# Digital_Isolation.net
KiCad netlist of a schematic drawn in Altium Designer
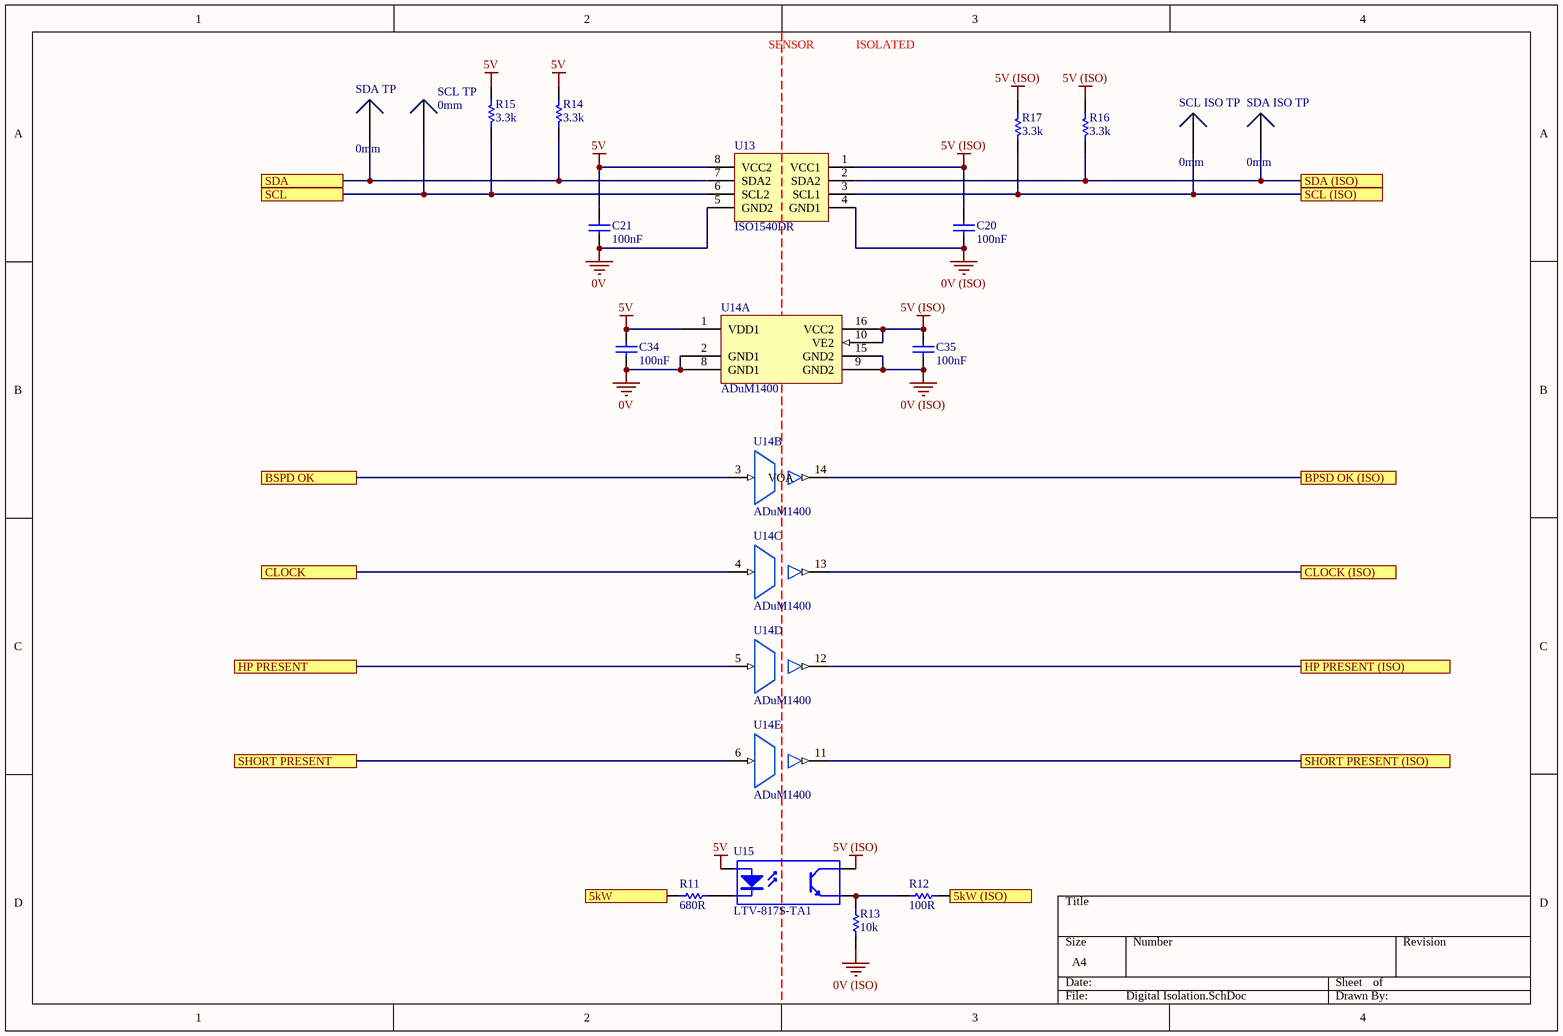
[diagram p0: Digital Isolation.SchDoc]

(export (version "E")
  (design (tool "Eeschema 10.0.6"))
  (components
    (comp (ref "C20")
      (value "100nF")
      (footprint "0805")
      (fields
        (field (name "PART NUMBER") "GCM21BR71E104KA37L")
        (field (name "TOLERANCE") "10%")
        (field (name "MANUFACTURER") "muRata")
      )
      (libsource (lib "ts_20-standard-library") (part "Capacitor"))
    )
    (comp (ref "C21")
      (value "100nF")
      (footprint "0805")
      (fields
        (field (name "PART NUMBER") "GCM21BR71E104KA37L")
        (field (name "TOLERANCE") "10%")
        (field (name "MANUFACTURER") "muRata")
      )
      (libsource (lib "ts_20-standard-library") (part "Capacitor"))
    )
    (comp (ref "C34")
      (value "100nF")
      (footprint "0805")
      (fields
        (field (name "PART NUMBER") "GCM21BR71E104KA37L")
        (field (name "TOLERANCE") "10%")
        (field (name "MANUFACTURER") "muRata")
      )
      (libsource (lib "ts_20-standard-library") (part "Capacitor"))
    )
    (comp (ref "C35")
      (value "100nF")
      (footprint "0805")
      (fields
        (field (name "PART NUMBER") "GCM21BR71E104KA37L")
        (field (name "TOLERANCE") "10%")
        (field (name "MANUFACTURER") "muRata")
      )
      (libsource (lib "ts_20-standard-library") (part "Capacitor"))
    )
    (comp (ref "R11")
      (value "680R")
      (footprint "0805")
      (fields
        (field (name "PART NUMBER") "RC0805FR07680RL")
        (field (name "MANUFACTURER") "YAGEO")
        (field (name "TOLERANCE") "0.01")
      )
      (libsource (lib "ts_20-standard-library") (part "Resistor"))
    )
    (comp (ref "R12")
      (value "100R")
      (footprint "0805")
      (fields
        (field (name "PART NUMBER") "RC0805FR07100RL")
        (field (name "MANUFACTURER") "YAGEO")
        (field (name "TOLERANCE") "0.01")
      )
      (libsource (lib "ts_20-standard-library") (part "Resistor"))
    )
    (comp (ref "R13")
      (value "10k")
      (footprint "0805")
      (fields
        (field (name "PART NUMBER") "RC0805FR0710KL")
        (field (name "MANUFACTURER") "YAGEO")
        (field (name "TOLERANCE") "0.01")
      )
      (libsource (lib "ts_20-standard-library") (part "Resistor"))
    )
    (comp (ref "R14")
      (value "3.3k")
      (footprint "0805")
      (fields
        (field (name "PART NUMBER") "RC0805FR073K3L")
        (field (name "MANUFACTURER") "YAGEO")
        (field (name "TOLERANCE") "0.01")
      )
      (libsource (lib "ts_20-standard-library") (part "Resistor"))
    )
    (comp (ref "R15")
      (value "3.3k")
      (footprint "0805")
      (fields
        (field (name "PART NUMBER") "RC0805FR073K3L")
        (field (name "MANUFACTURER") "YAGEO")
        (field (name "TOLERANCE") "0.01")
      )
      (libsource (lib "ts_20-standard-library") (part "Resistor"))
    )
    (comp (ref "R16")
      (value "3.3k")
      (footprint "0805")
      (fields
        (field (name "PART NUMBER") "RC0805FR073K3L")
        (field (name "MANUFACTURER") "YAGEO")
        (field (name "TOLERANCE") "0.01")
      )
      (libsource (lib "ts_20-standard-library") (part "Resistor"))
    )
    (comp (ref "R17")
      (value "3.3k")
      (footprint "0805")
      (fields
        (field (name "PART NUMBER") "RC0805FR073K3L")
        (field (name "MANUFACTURER") "YAGEO")
        (field (name "TOLERANCE") "0.01")
      )
      (libsource (lib "ts_20-standard-library") (part "Resistor"))
    )
    (comp (ref "SCL ISO TP")
      (value "0mm")
      (footprint "SMD Test Point")
      (fields (field (name "PART NUMBER") "SMD Test Point") (field (name "CONTACT") "NA"))
      (libsource (lib "ts_20-standard-connectors") (part "Test Point"))
    )
    (comp (ref "SCL TP")
      (value "0mm")
      (footprint "SMD Test Point")
      (fields (field (name "PART NUMBER") "SMD Test Point") (field (name "CONTACT") "NA"))
      (libsource (lib "ts_20-standard-connectors") (part "Test Point"))
    )
    (comp (ref "SDA ISO TP")
      (value "0mm")
      (footprint "SMD Test Point")
      (fields (field (name "PART NUMBER") "SMD Test Point") (field (name "CONTACT") "NA"))
      (libsource (lib "ts_20-standard-connectors") (part "Test Point"))
    )
    (comp (ref "SDA TP")
      (value "0mm")
      (footprint "SMD Test Point")
      (fields (field (name "PART NUMBER") "SMD Test Point") (field (name "CONTACT") "NA"))
      (libsource (lib "ts_20-standard-connectors") (part "Test Point"))
    )
    (comp (ref "U13")
      (value "ISO1540DR")
      (footprint "TI 8-SOIC")
      (description "I2C Digital Isolator (Multichannel)")
      (fields
        (field (name "MANUFACTURER") "Texas Instruments")
        (field (name "DIGIKEY PART NUMBER") "296-34871-1-ND")
      )
      (libsource (lib "ts_20-standard-library") (part "ISO1540DR"))
    )
    (comp (ref "U14")
      (value "ADuM1400")
      (footprint "AD 16-SOIC")
      (fields
        (field (name "MANUFACTURER") "Analog Devices")
        (field (name "DIGIKEY PART NUMBER") "ADUM1400WSRWZ-ND")
      )
      (libsource (lib "ts_20-standard-library") (part "ADuM1400"))
    )
    (comp (ref "U15")
      (value "LTV-817S-TA1")
      (footprint "ON 4-SMD")
      (description "35V 50ma Optocoupler (VF=1.2V)")
      (fields
        (field (name "MANUFACTURER") "Lite-On Inc")
        (field (name "DIGIKEY PART NUMBER") "160-1893-2-ND")
      )
      (libsource (lib "ts_20-standard-library") (part "LTV-817S-TA1"))
    )
  )
  (nets
    (net (code "1") (name "/5kW") (class "Default")
      (node (ref "R11") (pin "2") (pinfunction "2_2") (pintype "passive"))
    )
    (net (code "2") (name "/5kW (ISO)") (class "Default")
      (node (ref "R12") (pin "2") (pinfunction "2_2") (pintype "passive"))
    )
    (net (code "3") (name "/BPSD OK (ISO)") (class "Default")
      (node (ref "U14") (pin "14") (pinfunction "VOA_14") (pintype "output"))
    )
    (net (code "4") (name "/BSPD OK") (class "Default")
      (node (ref "U14") (pin "3") (pinfunction "VIA_3") (pintype "input"))
    )
    (net (code "5") (name "/CLOCK") (class "Default")
      (node (ref "U14") (pin "4") (pinfunction "VIB_4") (pintype "input"))
    )
    (net (code "6") (name "/CLOCK (ISO)") (class "Default")
      (node (ref "U14") (pin "13") (pinfunction "VOB_13") (pintype "output"))
    )
    (net (code "7") (name "/HP PRESENT") (class "Default")
      (node (ref "U14") (pin "5") (pinfunction "VIC_5") (pintype "input"))
    )
    (net (code "8") (name "/HP PRESENT (ISO)") (class "Default")
      (node (ref "U14") (pin "12") (pinfunction "VOC_12") (pintype "output"))
    )
    (net (code "9") (name "/SCL") (class "Default")
      (node (ref "R15") (pin "1") (pinfunction "1_1") (pintype "passive"))
      (node (ref "SCL TP") (pin "1") (pinfunction "1_1") (pintype "passive"))
      (node (ref "U13") (pin "6") (pinfunction "SCL2_6") (pintype "power_in"))
    )
    (net (code "10") (name "/SCL (ISO)") (class "Default")
      (node (ref "R17") (pin "1") (pinfunction "1_1") (pintype "passive"))
      (node (ref "SCL ISO TP") (pin "1") (pinfunction "1_1") (pintype "passive"))
      (node (ref "U13") (pin "3") (pinfunction "SCL1_3") (pintype "power_in"))
    )
    (net (code "11") (name "/SDA") (class "Default")
      (node (ref "R14") (pin "1") (pinfunction "1_1") (pintype "passive"))
      (node (ref "SDA TP") (pin "1") (pinfunction "1_1") (pintype "passive"))
      (node (ref "U13") (pin "7") (pinfunction "SDA2_7") (pintype "power_in"))
    )
    (net (code "12") (name "/SDA (ISO)") (class "Default")
      (node (ref "R16") (pin "1") (pinfunction "1_1") (pintype "passive"))
      (node (ref "SDA ISO TP") (pin "1") (pinfunction "1_1") (pintype "passive"))
      (node (ref "U13") (pin "2") (pinfunction "SDA2_2") (pintype "power_in"))
    )
    (net (code "13") (name "/SHORT PRESENT") (class "Default")
      (node (ref "U14") (pin "6") (pinfunction "VID_6") (pintype "input"))
    )
    (net (code "14") (name "/SHORT PRESENT (ISO)") (class "Default")
      (node (ref "U14") (pin "11") (pinfunction "VOD_11") (pintype "output"))
    )
    (net (code "15") (name "0V") (class "Default")
      (node (ref "C21") (pin "1") (pinfunction "1_1") (pintype "passive"))
      (node (ref "C34") (pin "1") (pinfunction "1_1") (pintype "passive"))
      (node (ref "U13") (pin "5") (pinfunction "GND2_5") (pintype "power_in"))
      (node (ref "U14") (pin "2") (pinfunction "GND1_2") (pintype "power_in"))
      (node (ref "U14") (pin "8") (pinfunction "GND1_8") (pintype "power_in"))
    )
    (net (code "16") (name "0V (ISO)") (class "Default")
      (node (ref "C20") (pin "1") (pinfunction "1_1") (pintype "passive"))
      (node (ref "C35") (pin "1") (pinfunction "1_1") (pintype "passive"))
      (node (ref "R13") (pin "1") (pinfunction "1_1") (pintype "passive"))
      (node (ref "U13") (pin "4") (pinfunction "GND1_4") (pintype "power_in"))
      (node (ref "U14") (pin "15") (pinfunction "GND2_15") (pintype "power_in"))
      (node (ref "U14") (pin "9") (pinfunction "GND2_9") (pintype "power_in"))
    )
    (net (code "17") (name "5V") (class "Default")
      (node (ref "C21") (pin "2") (pinfunction "2_2") (pintype "passive"))
      (node (ref "C34") (pin "2") (pinfunction "2_2") (pintype "passive"))
      (node (ref "R14") (pin "2") (pinfunction "2_2") (pintype "passive"))
      (node (ref "R15") (pin "2") (pinfunction "2_2") (pintype "passive"))
      (node (ref "U13") (pin "8") (pinfunction "VCC2_8") (pintype "power_in"))
      (node (ref "U14") (pin "1") (pinfunction "VDD1_1") (pintype "power_in"))
      (node (ref "U15") (pin "1") (pinfunction "A_1") (pintype "passive"))
    )
    (net (code "18") (name "5V (ISO)") (class "Default")
      (node (ref "C20") (pin "2") (pinfunction "2_2") (pintype "passive"))
      (node (ref "C35") (pin "2") (pinfunction "2_2") (pintype "passive"))
      (node (ref "R16") (pin "2") (pinfunction "2_2") (pintype "passive"))
      (node (ref "R17") (pin "2") (pinfunction "2_2") (pintype "passive"))
      (node (ref "U13") (pin "1") (pinfunction "VCC1_1") (pintype "power_in"))
      (node (ref "U14") (pin "10") (pinfunction "VE2_10") (pintype "input"))
      (node (ref "U14") (pin "16") (pinfunction "VCC2_16") (pintype "power_in"))
      (node (ref "U15") (pin "4") (pinfunction "C_4") (pintype "passive"))
    )
    (net (code "19") (name "Net-(U15-E)") (class "Default")
      (node (ref "R12") (pin "1") (pinfunction "1_1") (pintype "passive"))
      (node (ref "R13") (pin "2") (pinfunction "2_2") (pintype "passive"))
      (node (ref "U15") (pin "3") (pinfunction "E_3") (pintype "passive"))
    )
    (net (code "20") (name "Net-(U15-K)") (class "Default")
      (node (ref "R11") (pin "1") (pinfunction "1_1") (pintype "passive"))
      (node (ref "U15") (pin "2") (pinfunction "K_2") (pintype "passive"))
    )
  )
)
